# Power.net
KiCad netlist of a schematic drawn in Altium Designer
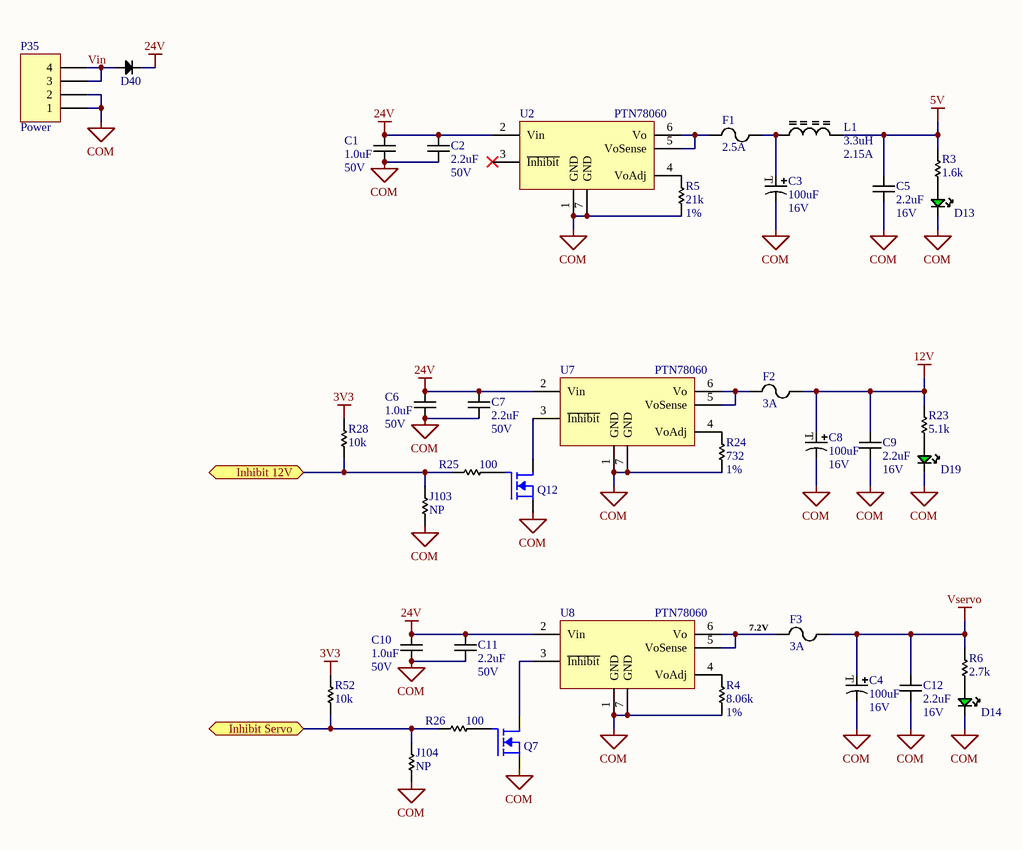
[diagram p0: Power.SchDoc]

(export (version "E")
  (design (tool "Eeschema 10.0.6"))
  (components
    (comp (ref "C1")
      (value "1.0uF")
      (footprint "0805 - Cap Non-Polarized")
      (description "CAP CER 1UF 50V 10% X7R 0805")
      (fields
        (field (name "PART NUMBER") "Cap-Samsung-CL-50V-1.0uF-0805-10%")
        (field (name "MANUFACTURER") "Samsung Electro-Mechanics America, Inc")
        (field (name "VOLTAGE") "50V")
        (field (name "CREATED BY") "Pier-Yves")
      )
      (libsource (lib "local") (part "Cap"))
    )
    (comp (ref "C2")
      (value "2.2uF")
      (footprint "0805 - Cap Non-Polarized")
      (description "CAP CER 2.2UF 50V 10% X5R 0805")
      (fields
        (field (name "PART NUMBER") "Cap-Samsung-CL-50V-2.2uF-0805-10%")
        (field (name "MANUFACTURER") "Samsung Electro-Mechanics America, Inc")
        (field (name "VOLTAGE") "50V")
        (field (name "CREATED BY") "Pier-Yves")
      )
      (libsource (lib "local") (part "Cap"))
    )
    (comp (ref "C3")
      (value "100uF")
      (footprint "Tantalum - Case D")
      (description "CAP TANT 100 16V 10% 2917")
      (fields
        (field (name "PART NUMBER") "Kemet-T491-100uF-16V-700 mOhm")
        (field (name "MANUFACTURER") "Kemet")
        (field (name "VOLTAGE") "16V")
        (field (name "CREATED BY") "Frederic")
      )
      (libsource (lib "local") (part "Cap Tantal"))
    )
    (comp (ref "C4")
      (value "100uF")
      (footprint "Tantalum - Case D")
      (description "CAP TANT 100 16V 10% 2917")
      (fields
        (field (name "PART NUMBER") "Kemet-T491-100uF-16V-700 mOhm")
        (field (name "MANUFACTURER") "Kemet")
        (field (name "VOLTAGE") "16V")
        (field (name "CREATED BY") "Frederic")
      )
      (libsource (lib "local") (part "Cap Tantal"))
    )
    (comp (ref "C5")
      (value "2.2uF")
      (footprint "0805 - Cap Non-Polarized")
      (description "CAP CER 2.2UF 16V 10% X7R 0805")
      (fields
        (field (name "PART NUMBER") "Cap-TDK-CGA-2.2uF-0805")
        (field (name "MANUFACTURER") "TDK")
        (field (name "VOLTAGE") "16V")
        (field (name "CREATED BY") "Pier-Yves")
      )
      (libsource (lib "local") (part "Cap"))
    )
    (comp (ref "C6")
      (value "1.0uF")
      (footprint "0805 - Cap Non-Polarized")
      (description "CAP CER 1UF 50V 10% X7R 0805")
      (fields
        (field (name "PART NUMBER") "Cap-Samsung-CL-50V-1.0uF-0805-10%")
        (field (name "MANUFACTURER") "Samsung Electro-Mechanics America, Inc")
        (field (name "VOLTAGE") "50V")
        (field (name "CREATED BY") "Pier-Yves")
      )
      (libsource (lib "local") (part "Cap"))
    )
    (comp (ref "C7")
      (value "2.2uF")
      (footprint "0805 - Cap Non-Polarized")
      (description "CAP CER 2.2UF 50V 10% X5R 0805")
      (fields
        (field (name "PART NUMBER") "Cap-Samsung-CL-50V-2.2uF-0805-10%")
        (field (name "MANUFACTURER") "Samsung Electro-Mechanics America, Inc")
        (field (name "VOLTAGE") "50V")
        (field (name "CREATED BY") "Pier-Yves")
      )
      (libsource (lib "local") (part "Cap"))
    )
    (comp (ref "C8")
      (value "100uF")
      (footprint "Tantalum - Case D")
      (description "CAP TANT 100 16V 10% 2917")
      (fields
        (field (name "PART NUMBER") "Kemet-T491-100uF-16V-700 mOhm")
        (field (name "MANUFACTURER") "Kemet")
        (field (name "VOLTAGE") "16V")
        (field (name "CREATED BY") "Frederic")
      )
      (libsource (lib "local") (part "Cap Tantal"))
    )
    (comp (ref "C9")
      (value "2.2uF")
      (footprint "0805 - Cap Non-Polarized")
      (description "CAP CER 2.2UF 16V 10% X7R 0805")
      (fields
        (field (name "PART NUMBER") "Cap-TDK-CGA-2.2uF-0805")
        (field (name "MANUFACTURER") "TDK")
        (field (name "VOLTAGE") "16V")
        (field (name "CREATED BY") "Pier-Yves")
      )
      (libsource (lib "local") (part "Cap"))
    )
    (comp (ref "C10")
      (value "1.0uF")
      (footprint "0805 - Cap Non-Polarized")
      (description "CAP CER 1UF 50V 10% X7R 0805")
      (fields
        (field (name "PART NUMBER") "Cap-Samsung-CL-50V-1.0uF-0805-10%")
        (field (name "MANUFACTURER") "Samsung Electro-Mechanics America, Inc")
        (field (name "VOLTAGE") "50V")
        (field (name "CREATED BY") "Pier-Yves")
      )
      (libsource (lib "local") (part "Cap"))
    )
    (comp (ref "C11")
      (value "2.2uF")
      (footprint "0805 - Cap Non-Polarized")
      (description "CAP CER 2.2UF 50V 10% X5R 0805")
      (fields
        (field (name "PART NUMBER") "Cap-Samsung-CL-50V-2.2uF-0805-10%")
        (field (name "MANUFACTURER") "Samsung Electro-Mechanics America, Inc")
        (field (name "VOLTAGE") "50V")
        (field (name "CREATED BY") "Pier-Yves")
      )
      (libsource (lib "local") (part "Cap"))
    )
    (comp (ref "C12")
      (value "2.2uF")
      (footprint "0805 - Cap Non-Polarized")
      (description "CAP CER 2.2UF 16V 10% X7R 0805")
      (fields
        (field (name "PART NUMBER") "Cap-TDK-CGA-2.2uF-0805")
        (field (name "MANUFACTURER") "TDK")
        (field (name "VOLTAGE") "16V")
        (field (name "CREATED BY") "Pier-Yves")
      )
      (libsource (lib "local") (part "Cap"))
    )
    (comp (ref "D13")
      (value "Green")
      (footprint "0603 - Led Green")
      (description "LED SMARTLED GREEN 570NM 0603")
      (fields
        (field (name "PART NUMBER") "LED-Green-2mA-lowBrigthness-0603")
        (field (name "MANUFACTURER") "OSRAM Opto Semiconductor")
        (field (name "CREATED BY") "Pier-Yves")
      )
      (libsource (lib "local") (part "Led Green"))
    )
    (comp (ref "D14")
      (value "Green")
      (footprint "0603 - Led Green")
      (description "LED SMARTLED GREEN 570NM 0603")
      (fields
        (field (name "PART NUMBER") "LED-Green-2mA-lowBrigthness-0603")
        (field (name "MANUFACTURER") "OSRAM Opto Semiconductor")
        (field (name "CREATED BY") "Pier-Yves")
      )
      (libsource (lib "local") (part "Led Green"))
    )
    (comp (ref "D19")
      (value "Green")
      (footprint "0603 - Led Green")
      (description "LED SMARTLED GREEN 570NM 0603")
      (fields
        (field (name "PART NUMBER") "LED-Green-2mA-lowBrigthness-0603")
        (field (name "MANUFACTURER") "OSRAM Opto Semiconductor")
        (field (name "CREATED BY") "Pier-Yves")
      )
      (libsource (lib "local") (part "Led Green"))
    )
    (comp (ref "D40")
      (value "Diode")
      (footprint "DOS-214AB (SMC)")
      (description "DIODE GEN PURP 200V 10A DO214AB")
      (fields
        (field (name "PART NUMBER") "MicroCommercial-S10D-TP-10A-1.2V")
        (field (name "MANUFACTURER") "Micro Commercial Co.")
        (field (name "CREATED BY") "Pier-Yves")
      )
      (libsource (lib "local") (part "Diode"))
    )
    (comp (ref "F1")
      (value "2.5A")
      (footprint "Fuse - 1206")
      (description "FUSE 2.5A 125V 1206 FAST C1Q")
      (fields
        (field (name "PART NUMBER") "Fuse-1206-BelFuse-Fast-C1Q-2.5A")
        (field (name "MANUFACTURER") "Bel Fuse")
        (field (name "CREATED BY") "Pier-Yves")
      )
      (libsource (lib "local") (part "Fuse"))
    )
    (comp (ref "F2")
      (value "3A")
      (footprint "Fuse - 1206")
      (description "FUSE SLOW 32VDC 3A 1206")
      (fields
        (field (name "PART NUMBER") "Fuse-1206-Bourns-Slow-SinglFuse_SF-1206S-3A")
        (field (name "MANUFACTURER") "Bourns Inc.")
        (field (name "CREATED BY") "Pier-Yves")
      )
      (libsource (lib "local") (part "Fuse"))
    )
    (comp (ref "F3")
      (value "3A")
      (footprint "Fuse - 1206")
      (description "FUSE SLOW 32VDC 3A 1206")
      (fields
        (field (name "PART NUMBER") "Fuse-1206-Bourns-Slow-SinglFuse_SF-1206S-3A")
        (field (name "MANUFACTURER") "Bourns Inc.")
        (field (name "CREATED BY") "Pier-Yves")
      )
      (libsource (lib "local") (part "Fuse"))
    )
    (comp (ref "J103")
      (value "NP")
      (footprint "0805 - Resistor")
      (description "RES 0.0 OHM 1/8W JUMP 0805")
      (fields
        (field (name "PART NUMBER") "Jumper-0805")
        (field (name "MANUFACTURER") "Stackpole electronic")
        (field (name "CREATED BY") "Pier-Yves")
      )
      (libsource (lib "local") (part "Res"))
    )
    (comp (ref "J104")
      (value "NP")
      (footprint "0805 - Resistor")
      (description "RES 0.0 OHM 1/8W JUMP 0805")
      (fields
        (field (name "PART NUMBER") "Jumper-0805")
        (field (name "MANUFACTURER") "Stackpole electronic")
        (field (name "CREATED BY") "Pier-Yves")
      )
      (libsource (lib "local") (part "Res"))
    )
    (comp (ref "L1")
      (value "3.3uH")
      (footprint "SRN403")
      (description "INDUCTOR POWER 3.3UH 2.15A 0403")
      (fields
        (field (name "PART NUMBER") "Ind-Bourns-SRN403-20%-3.3uH")
        (field (name "MANUFACTURER") "Bourns Inc.")
        (field (name "CURRENT") "2.15A")
        (field (name "CREATED BY") "Pier-Yves")
      )
      (libsource (lib "local") (part "Inductor_core"))
    )
    (comp (ref "P35")
      (value "Power")
      (footprint "OSTOQ045451")
      (description "TERM BLOCK HDR 5.08MM 4POS PCB")
      (fields
        (field (name "PART NUMBER") "ConnBlock-200mils-RightAngle-THT-4pos")
        (field (name "VOLTAGE") "300V")
        (field (name "PUBLISHER") "Altium Limited")
        (field (name "CREATED BY") "Pier-Yves")
      )
      (libsource (lib "local") (part "Header 1X4"))
    )
    (comp (ref "Q7")
      (value "MOSFET_N")
      (footprint "SOT23-3")
      (description "MosFET Channel-N SOT-23-3 3.3A")
      (fields
        (field (name "PART NUMBER") "2N7002")
        (field (name "MANUFACTURER") "Vishay Siliconix")
        (field (name "CREATED BY") "Pier-Yves")
      )
      (libsource (lib "local") (part "MOSFET_N_GSD"))
    )
    (comp (ref "Q12")
      (value "MOSFET_N")
      (footprint "SOT23-3")
      (description "MosFET Channel-N SOT-23-3 3.3A")
      (fields
        (field (name "PART NUMBER") "2N7002")
        (field (name "MANUFACTURER") "Vishay Siliconix")
        (field (name "CREATED BY") "Pier-Yves")
      )
      (libsource (lib "local") (part "MOSFET_N_GSD"))
    )
    (comp (ref "R3")
      (value "1.6k")
      (footprint "0805 - Resistor")
      (description "RES 1.6K OHM 1/8W 5% 0805 SMD")
      (fields
        (field (name "PART NUMBER") "Yagao-RC0805-1.6k")
        (field (name "MANUFACTURER") "Yagao")
        (field (name "CREATED BY") "Pier-Yves")
      )
      (libsource (lib "local") (part "Res"))
    )
    (comp (ref "R4")
      (value "8.06k")
      (footprint "0805 - Resistor")
      (description "RES 8.06K OHM 1/8W 1% 0805 SMD")
      (fields
        (field (name "PART NUMBER") "Yagao-RC0805-1%-8.06k")
        (field (name "MANUFACTURER") "Yagao")
        (field (name "TOLERANCE") "1%")
        (field (name "CREATED BY") "Pier-Yves")
      )
      (libsource (lib "local") (part "Res"))
    )
    (comp (ref "R5")
      (value "21k")
      (footprint "0805 - Resistor")
      (description "RES 21.0K OHM 1/8W 1% 0805 SMD")
      (fields
        (field (name "PART NUMBER") "Yagao-RC0805-1%-21k")
        (field (name "MANUFACTURER") "Yagao")
        (field (name "TOLERANCE") "1%")
        (field (name "CREATED BY") "Pier-Yves")
      )
      (libsource (lib "local") (part "Res"))
    )
    (comp (ref "R6")
      (value "2.7k")
      (footprint "0805 - Resistor")
      (description "RES 2.7K OHM 1/8W 5% 0805 SMD")
      (fields
        (field (name "PART NUMBER") "Yagao-RC0805-2.7k")
        (field (name "MANUFACTURER") "Yagao")
        (field (name "CREATED BY") "Pier-Yves")
      )
      (libsource (lib "local") (part "Res"))
    )
    (comp (ref "R23")
      (value "5.1k")
      (footprint "0805 - Resistor")
      (description "RES 5.1K OHM 1/8W 5% 0805 SMD")
      (fields
        (field (name "PART NUMBER") "Yagao-RC0805-5.1k")
        (field (name "MANUFACTURER") "Yagao")
        (field (name "CREATED BY") "Pier-Yves")
      )
      (libsource (lib "local") (part "Res"))
    )
    (comp (ref "R24")
      (value "732")
      (footprint "0805 - Resistor")
      (description "RES 732 OHM 1/8W 1% 0805 SMD")
      (fields
        (field (name "PART NUMBER") "Yagao-RC0805-1%-732")
        (field (name "MANUFACTURER") "Yagao")
        (field (name "TOLERANCE") "1%")
        (field (name "CREATED BY") "Pier-Yves")
      )
      (libsource (lib "local") (part "Res"))
    )
    (comp (ref "R25")
      (value "100")
      (footprint "0805 - Resistor")
      (description "RES 100 OHM 1/8W 5% 0805 SMD")
      (fields
        (field (name "PART NUMBER") "Yagao-RC0805-100")
        (field (name "MANUFACTURER") "Yagao")
        (field (name "CREATED BY") "Pier-Yves")
      )
      (libsource (lib "local") (part "Res"))
    )
    (comp (ref "R26")
      (value "100")
      (footprint "0805 - Resistor")
      (description "RES 100 OHM 1/8W 5% 0805 SMD")
      (fields
        (field (name "PART NUMBER") "Yagao-RC0805-100")
        (field (name "MANUFACTURER") "Yagao")
        (field (name "CREATED BY") "Pier-Yves")
      )
      (libsource (lib "local") (part "Res"))
    )
    (comp (ref "R28")
      (value "10k")
      (footprint "0805 - Resistor")
      (description "RES 10K OHM 1/8W 5% 0805 SMD")
      (fields
        (field (name "PART NUMBER") "Yagao-RC0805-10k")
        (field (name "MANUFACTURER") "Yagao")
        (field (name "CREATED BY") "Pier-Yves")
      )
      (libsource (lib "local") (part "Res"))
    )
    (comp (ref "R52")
      (value "10k")
      (footprint "0805 - Resistor")
      (description "RES 10K OHM 1/8W 5% 0805 SMD")
      (fields
        (field (name "PART NUMBER") "Yagao-RC0805-10k")
        (field (name "MANUFACTURER") "Yagao")
        (field (name "CREATED BY") "Pier-Yves")
      )
      (libsource (lib "local") (part "Res"))
    )
    (comp (ref "U2")
      (value "PTN78060")
      (footprint "PTN78060W-THT")
      (description "REG SW 2.5-12.6V 3A HORZ T/H")
      (fields
        (field (name "PART NUMBER") "PTN78060WAH")
        (field (name "MANUFACTURER") "Texas Instrument")
        (field (name "CREATED BY") "Pier-Yves")
      )
      (libsource (lib "local") (part "PTN78060"))
    )
    (comp (ref "U7")
      (value "PTN78060")
      (footprint "PTN78060W-THT")
      (description "REG SW 2.5-12.6V 3A HORZ T/H")
      (fields
        (field (name "PART NUMBER") "PTN78060WAH")
        (field (name "MANUFACTURER") "Texas Instrument")
        (field (name "CREATED BY") "Pier-Yves")
      )
      (libsource (lib "local") (part "PTN78060"))
    )
    (comp (ref "U8")
      (value "PTN78060")
      (footprint "PTN78060W-THT")
      (description "REG SW 2.5-12.6V 3A HORZ T/H")
      (fields
        (field (name "PART NUMBER") "PTN78060WAH")
        (field (name "MANUFACTURER") "Texas Instrument")
        (field (name "CREATED BY") "Pier-Yves")
      )
      (libsource (lib "local") (part "PTN78060"))
    )
  )
  (nets
    (net (code "1") (name "/Inhibit 12V") (class "Default")
      (node (ref "J103") (pin "1") (pinfunction "1_1") (pintype "passive"))
      (node (ref "R25") (pin "2") (pinfunction "2_2") (pintype "passive"))
      (node (ref "R28") (pin "2") (pinfunction "2_2") (pintype "passive"))
    )
    (net (code "2") (name "/Inhibit Servo") (class "Default")
      (node (ref "J104") (pin "1") (pinfunction "1_1") (pintype "passive"))
      (node (ref "R26") (pin "2") (pinfunction "2_2") (pintype "passive"))
      (node (ref "R52") (pin "2") (pinfunction "2_2") (pintype "passive"))
    )
    (net (code "3") (name "/Vin") (class "Default")
      (node (ref "D40") (pin "1") (pinfunction "A_1") (pintype "passive"))
      (node (ref "P35") (pin "3") (pinfunction "3_3") (pintype "passive"))
      (node (ref "P35") (pin "4") (pinfunction "4_4") (pintype "passive"))
    )
    (net (code "4") (name "3V3") (class "Default")
      (node (ref "R28") (pin "1") (pinfunction "1_1") (pintype "passive"))
      (node (ref "R52") (pin "1") (pinfunction "1_1") (pintype "passive"))
    )
    (net (code "5") (name "5V") (class "Default")
      (node (ref "C5") (pin "2") (pinfunction "2_2") (pintype "passive"))
      (node (ref "L1") (pin "2") (pinfunction "2_2") (pintype "passive"))
      (node (ref "R3") (pin "1") (pinfunction "1_1") (pintype "passive"))
    )
    (net (code "6") (name "12V") (class "Default")
      (node (ref "C8") (pin "1") (pinfunction "1_1") (pintype "passive"))
      (node (ref "C9") (pin "2") (pinfunction "2_2") (pintype "passive"))
      (node (ref "F2") (pin "1") (pinfunction "1_1") (pintype "passive"))
      (node (ref "R23") (pin "1") (pinfunction "1_1") (pintype "passive"))
    )
    (net (code "7") (name "24V") (class "Default")
      (node (ref "C1") (pin "1") (pinfunction "1_1") (pintype "passive"))
      (node (ref "C10") (pin "1") (pinfunction "1_1") (pintype "passive"))
      (node (ref "C11") (pin "1") (pinfunction "1_1") (pintype "passive"))
      (node (ref "C2") (pin "1") (pinfunction "1_1") (pintype "passive"))
      (node (ref "C6") (pin "1") (pinfunction "1_1") (pintype "passive"))
      (node (ref "C7") (pin "1") (pinfunction "1_1") (pintype "passive"))
      (node (ref "D40") (pin "2") (pinfunction "K_2") (pintype "passive"))
      (node (ref "U2") (pin "2") (pinfunction "Vin_2") (pintype "passive"))
      (node (ref "U7") (pin "2") (pinfunction "Vin_2") (pintype "passive"))
      (node (ref "U8") (pin "2") (pinfunction "Vin_2") (pintype "passive"))
    )
    (net (code "8") (name "COM") (class "Default")
      (node (ref "C1") (pin "2") (pinfunction "2_2") (pintype "passive"))
      (node (ref "C10") (pin "2") (pinfunction "2_2") (pintype "passive"))
      (node (ref "C11") (pin "2") (pinfunction "2_2") (pintype "passive"))
      (node (ref "C12") (pin "1") (pinfunction "1_1") (pintype "passive"))
      (node (ref "C2") (pin "2") (pinfunction "2_2") (pintype "passive"))
      (node (ref "C3") (pin "2") (pinfunction "2_2") (pintype "passive"))
      (node (ref "C4") (pin "2") (pinfunction "2_2") (pintype "passive"))
      (node (ref "C5") (pin "1") (pinfunction "1_1") (pintype "passive"))
      (node (ref "C6") (pin "2") (pinfunction "2_2") (pintype "passive"))
      (node (ref "C7") (pin "2") (pinfunction "2_2") (pintype "passive"))
      (node (ref "C8") (pin "2") (pinfunction "2_2") (pintype "passive"))
      (node (ref "C9") (pin "1") (pinfunction "1_1") (pintype "passive"))
      (node (ref "D13") (pin "2") (pinfunction "K_2") (pintype "passive"))
      (node (ref "D14") (pin "2") (pinfunction "K_2") (pintype "passive"))
      (node (ref "D19") (pin "2") (pinfunction "K_2") (pintype "passive"))
      (node (ref "J103") (pin "2") (pinfunction "2_2") (pintype "passive"))
      (node (ref "J104") (pin "2") (pinfunction "2_2") (pintype "passive"))
      (node (ref "P35") (pin "1") (pinfunction "1_1") (pintype "passive"))
      (node (ref "P35") (pin "2") (pinfunction "2_2") (pintype "passive"))
      (node (ref "Q12") (pin "2") (pinfunction "S_2") (pintype "passive"))
      (node (ref "Q7") (pin "2") (pinfunction "S_2") (pintype "passive"))
      (node (ref "R24") (pin "1") (pinfunction "1_1") (pintype "passive"))
      (node (ref "R4") (pin "2") (pinfunction "2_2") (pintype "passive"))
      (node (ref "R5") (pin "2") (pinfunction "2_2") (pintype "passive"))
      (node (ref "U2") (pin "1") (pinfunction "GND_1") (pintype "passive"))
      (node (ref "U2") (pin "7") (pinfunction "GND_7") (pintype "passive"))
      (node (ref "U7") (pin "1") (pinfunction "GND_1") (pintype "passive"))
      (node (ref "U7") (pin "7") (pinfunction "GND_7") (pintype "passive"))
      (node (ref "U8") (pin "1") (pinfunction "GND_1") (pintype "passive"))
      (node (ref "U8") (pin "7") (pinfunction "GND_7") (pintype "passive"))
    )
    (net (code "9") (name "Net-(C3-Pad1)") (class "Default")
      (node (ref "C3") (pin "1") (pinfunction "1_1") (pintype "passive"))
      (node (ref "F1") (pin "1") (pinfunction "1_1") (pintype "passive"))
      (node (ref "L1") (pin "1") (pinfunction "1_1") (pintype "passive"))
    )
    (net (code "10") (name "Net-(D13-A)") (class "Default")
      (node (ref "D13") (pin "1") (pinfunction "A_1") (pintype "passive"))
      (node (ref "R3") (pin "2") (pinfunction "2_2") (pintype "passive"))
    )
    (net (code "11") (name "Net-(D14-A)") (class "Default")
      (node (ref "D14") (pin "1") (pinfunction "A_1") (pintype "passive"))
      (node (ref "R6") (pin "2") (pinfunction "2_2") (pintype "passive"))
    )
    (net (code "12") (name "Net-(D19-A)") (class "Default")
      (node (ref "D19") (pin "1") (pinfunction "A_1") (pintype "passive"))
      (node (ref "R23") (pin "2") (pinfunction "2_2") (pintype "passive"))
    )
    (net (code "13") (name "Net-(Q7-D)") (class "Default")
      (node (ref "Q7") (pin "3") (pinfunction "D_3") (pintype "passive"))
      (node (ref "U8") (pin "3") (pinfunction "~{Inhibit}_3") (pintype "passive"))
    )
    (net (code "14") (name "Net-(Q7-G)") (class "Default")
      (node (ref "Q7") (pin "1") (pinfunction "G_1") (pintype "passive"))
      (node (ref "R26") (pin "1") (pinfunction "1_1") (pintype "passive"))
    )
    (net (code "15") (name "Net-(Q12-D)") (class "Default")
      (node (ref "Q12") (pin "3") (pinfunction "D_3") (pintype "passive"))
      (node (ref "U7") (pin "3") (pinfunction "~{Inhibit}_3") (pintype "passive"))
    )
    (net (code "16") (name "Net-(Q12-G)") (class "Default")
      (node (ref "Q12") (pin "1") (pinfunction "G_1") (pintype "passive"))
      (node (ref "R25") (pin "1") (pinfunction "1_1") (pintype "passive"))
    )
    (net (code "17") (name "Net-(U2-Vo)") (class "Default")
      (node (ref "F1") (pin "2") (pinfunction "2_2") (pintype "passive"))
      (node (ref "U2") (pin "5") (pinfunction "VoSense_5") (pintype "passive"))
      (node (ref "U2") (pin "6") (pinfunction "Vo_6") (pintype "passive"))
    )
    (net (code "18") (name "Net-(U2-VoAdj)") (class "Default")
      (node (ref "R5") (pin "1") (pinfunction "1_1") (pintype "passive"))
      (node (ref "U2") (pin "4") (pinfunction "VoAdj_4") (pintype "passive"))
    )
    (net (code "19") (name "Net-(U7-Vo)") (class "Default")
      (node (ref "F2") (pin "2") (pinfunction "2_2") (pintype "passive"))
      (node (ref "U7") (pin "5") (pinfunction "VoSense_5") (pintype "passive"))
      (node (ref "U7") (pin "6") (pinfunction "Vo_6") (pintype "passive"))
    )
    (net (code "20") (name "Net-(U7-VoAdj)") (class "Default")
      (node (ref "R24") (pin "2") (pinfunction "2_2") (pintype "passive"))
      (node (ref "U7") (pin "4") (pinfunction "VoAdj_4") (pintype "passive"))
    )
    (net (code "21") (name "Net-(U8-Vo)") (class "Default")
      (node (ref "F3") (pin "2") (pinfunction "2_2") (pintype "passive"))
      (node (ref "U8") (pin "5") (pinfunction "VoSense_5") (pintype "passive"))
      (node (ref "U8") (pin "6") (pinfunction "Vo_6") (pintype "passive"))
    )
    (net (code "22") (name "Net-(U8-VoAdj)") (class "Default")
      (node (ref "R4") (pin "1") (pinfunction "1_1") (pintype "passive"))
      (node (ref "U8") (pin "4") (pinfunction "VoAdj_4") (pintype "passive"))
    )
    (net (code "23") (name "Vservo") (class "Default")
      (node (ref "C12") (pin "2") (pinfunction "2_2") (pintype "passive"))
      (node (ref "C4") (pin "1") (pinfunction "1_1") (pintype "passive"))
      (node (ref "F3") (pin "1") (pinfunction "1_1") (pintype "passive"))
      (node (ref "R6") (pin "1") (pinfunction "1_1") (pintype "passive"))
    )
    (net (code "24") (name "unconnected-(U2-~{Inhibit}-Pad3)") (class "Default")
      (node (ref "U2") (pin "3") (pinfunction "~{Inhibit}_3") (pintype "passive+no_connect"))
    )
  )
)
